# BatTest.net
KiCad netlist of a schematic drawn in Altium Designer
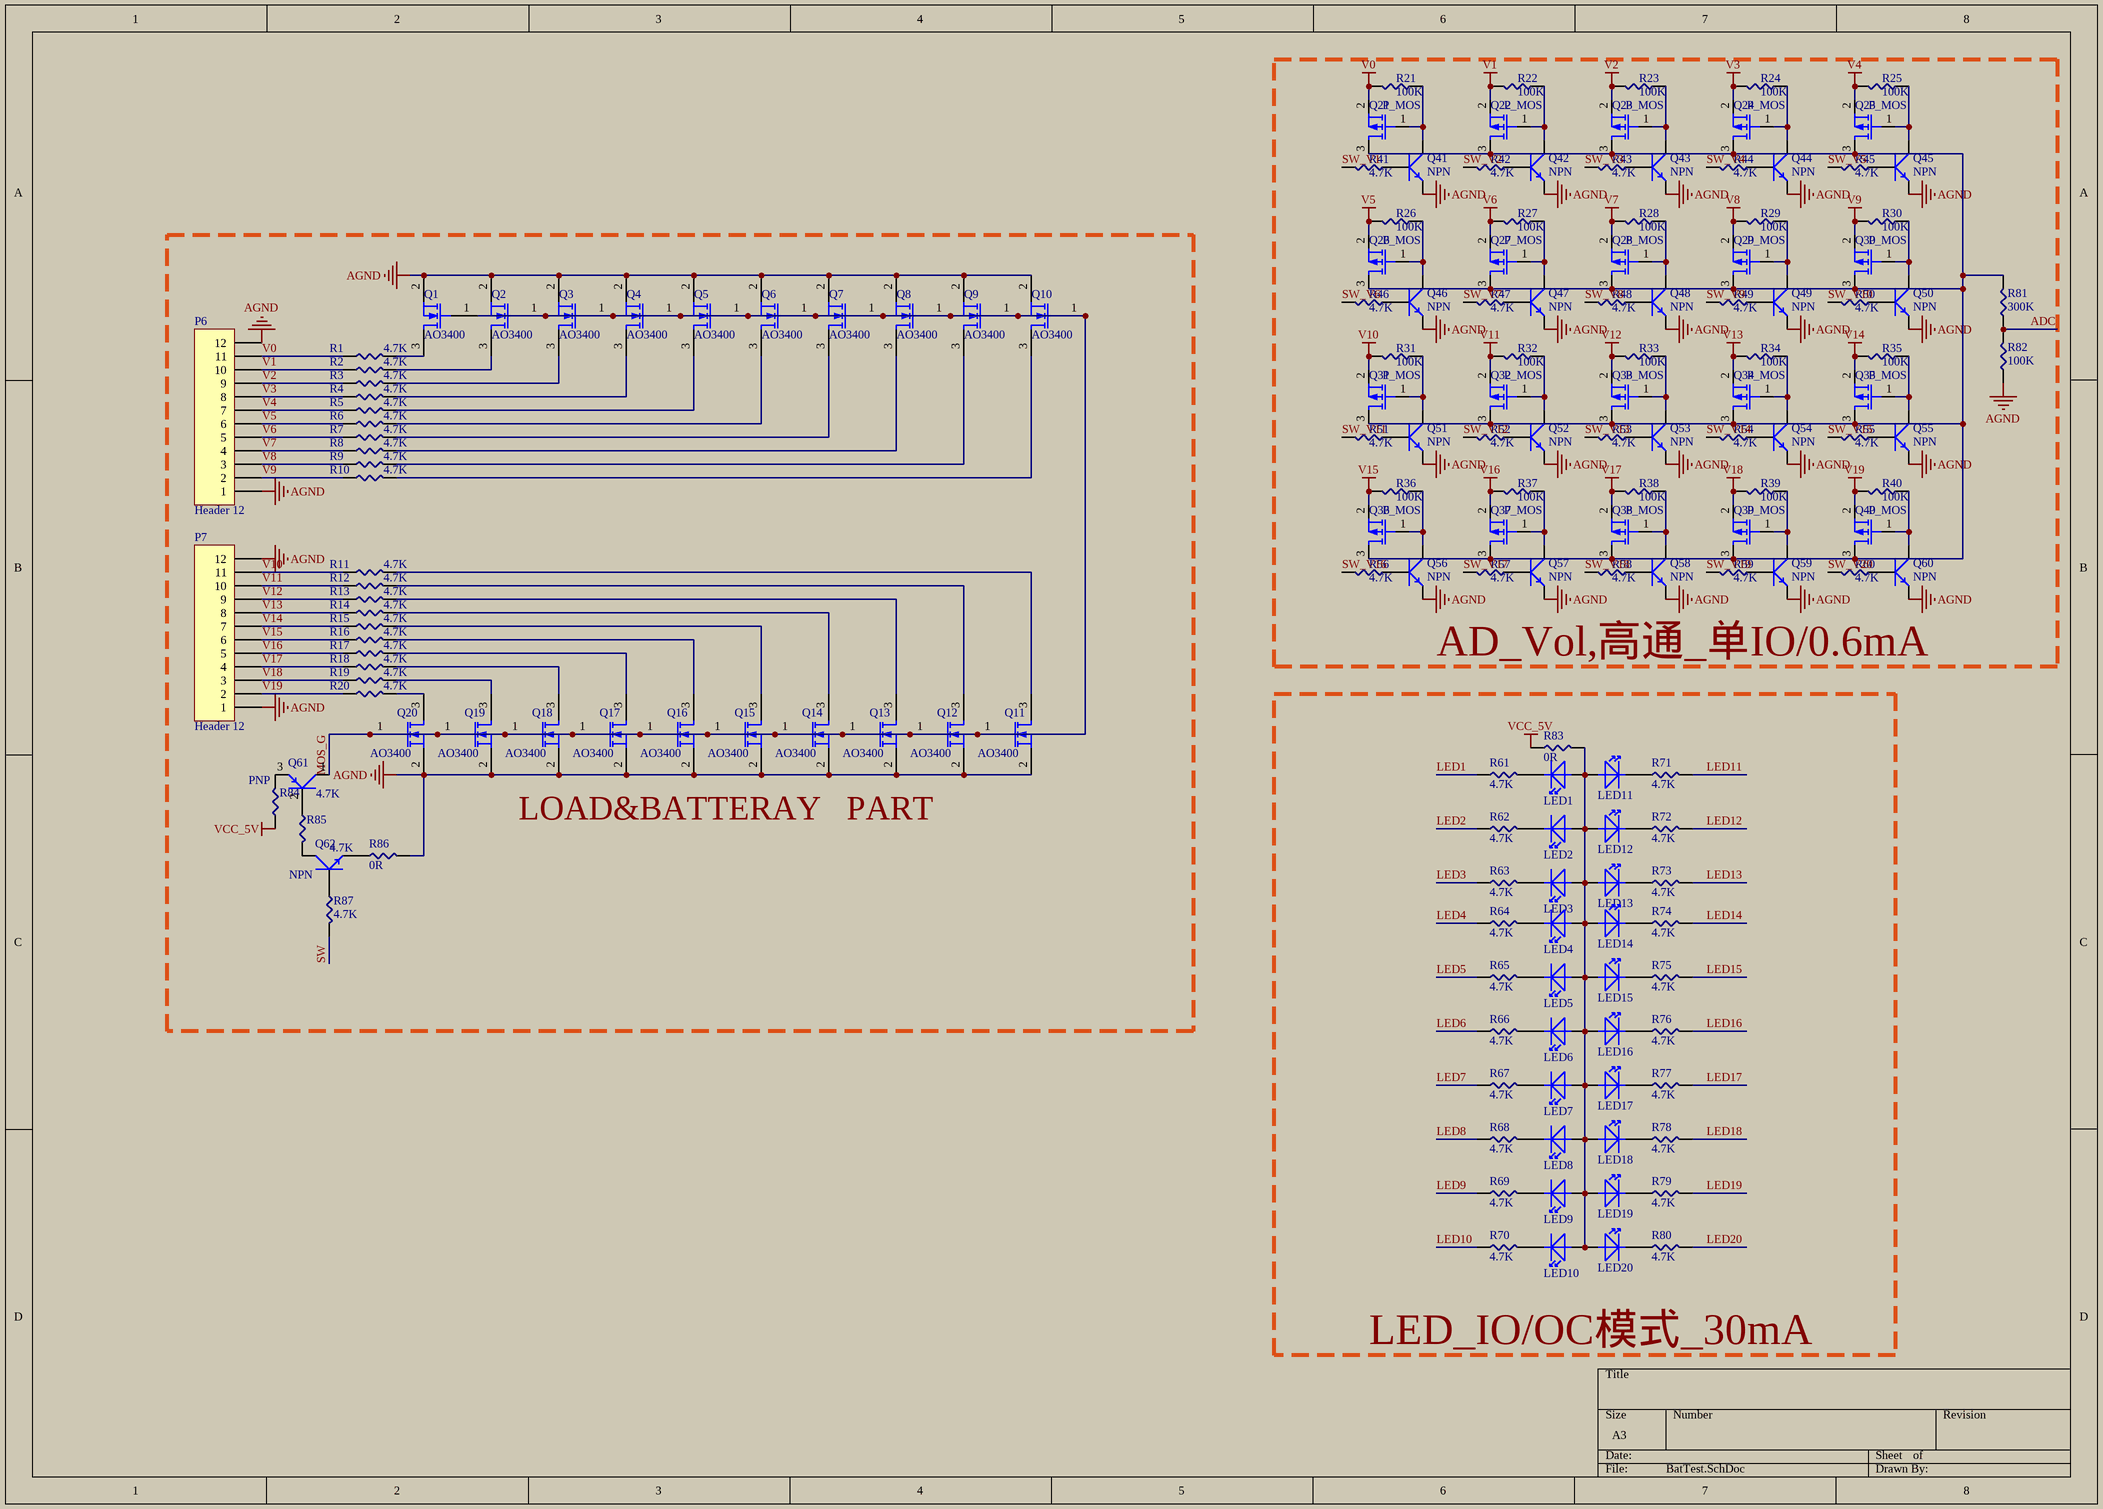
[diagram p0: BatTest.SchDoc]

(export (version "E")
  (design (tool "Eeschema 10.0.6"))
  (components
    (comp (ref "LED1")
      (value "SMD-LED")
      (footprint "DIODE-0603")
      (description "LED")
      (libsource (lib "XXDZ") (part "LED"))
    )
    (comp (ref "LED2")
      (value "SMD-LED")
      (footprint "DIODE-0603")
      (description "LED")
      (libsource (lib "XXDZ") (part "LED"))
    )
    (comp (ref "LED3")
      (value "SMD-LED")
      (footprint "DIODE-0603")
      (description "LED")
      (libsource (lib "XXDZ") (part "LED"))
    )
    (comp (ref "LED4")
      (value "SMD-LED")
      (footprint "DIODE-0603")
      (description "LED")
      (libsource (lib "XXDZ") (part "LED"))
    )
    (comp (ref "LED5")
      (value "SMD-LED")
      (footprint "DIODE-0603")
      (description "LED")
      (libsource (lib "XXDZ") (part "LED"))
    )
    (comp (ref "LED6")
      (value "SMD-LED")
      (footprint "DIODE-0603")
      (description "LED")
      (libsource (lib "XXDZ") (part "LED"))
    )
    (comp (ref "LED7")
      (value "SMD-LED")
      (footprint "DIODE-0603")
      (description "LED")
      (libsource (lib "XXDZ") (part "LED"))
    )
    (comp (ref "LED8")
      (value "SMD-LED")
      (footprint "DIODE-0603")
      (description "LED")
      (libsource (lib "XXDZ") (part "LED"))
    )
    (comp (ref "LED9")
      (value "SMD-LED")
      (footprint "DIODE-0603")
      (description "LED")
      (libsource (lib "XXDZ") (part "LED"))
    )
    (comp (ref "LED10")
      (value "SMD-LED")
      (footprint "DIODE-0603")
      (description "LED")
      (libsource (lib "XXDZ") (part "LED"))
    )
    (comp (ref "LED11")
      (value "SMD-LED")
      (footprint "DIODE-0603")
      (description "LED")
      (libsource (lib "XXDZ") (part "LED"))
    )
    (comp (ref "LED12")
      (value "SMD-LED")
      (footprint "DIODE-0603")
      (description "LED")
      (libsource (lib "XXDZ") (part "LED"))
    )
    (comp (ref "LED13")
      (value "SMD-LED")
      (footprint "DIODE-0603")
      (description "LED")
      (libsource (lib "XXDZ") (part "LED"))
    )
    (comp (ref "LED14")
      (value "SMD-LED")
      (footprint "DIODE-0603")
      (description "LED")
      (libsource (lib "XXDZ") (part "LED"))
    )
    (comp (ref "LED15")
      (value "SMD-LED")
      (footprint "DIODE-0603")
      (description "LED")
      (libsource (lib "XXDZ") (part "LED"))
    )
    (comp (ref "LED16")
      (value "SMD-LED")
      (footprint "DIODE-0603")
      (description "LED")
      (libsource (lib "XXDZ") (part "LED"))
    )
    (comp (ref "LED17")
      (value "SMD-LED")
      (footprint "DIODE-0603")
      (description "LED")
      (libsource (lib "XXDZ") (part "LED"))
    )
    (comp (ref "LED18")
      (value "SMD-LED")
      (footprint "DIODE-0603")
      (description "LED")
      (libsource (lib "XXDZ") (part "LED"))
    )
    (comp (ref "LED19")
      (value "SMD-LED")
      (footprint "DIODE-0603")
      (description "LED")
      (libsource (lib "XXDZ") (part "LED"))
    )
    (comp (ref "LED20")
      (value "SMD-LED")
      (footprint "DIODE-0603")
      (description "LED")
      (libsource (lib "XXDZ") (part "LED"))
    )
    (comp (ref "P6")
      (value "Header 12")
      (footprint "HDR1X12")
      (description "Header, 12-Pin")
      (fields (field (name "PUBLISHER") "Altium Limited"))
      (libsource (lib "Miscellaneous Connectors") (part "Header 12"))
    )
    (comp (ref "P7")
      (value "Header 12")
      (footprint "HDR1X12")
      (description "Header, 12-Pin")
      (fields (field (name "PUBLISHER") "Altium Limited"))
      (libsource (lib "Miscellaneous Connectors") (part "Header 12"))
    )
    (comp (ref "Q1") (value "AO3400") (footprint "SOT-23-MOS") (libsource (lib "MySchlib1") (part "N_MOS")))
    (comp (ref "Q2") (value "AO3400") (footprint "SOT-23-MOS") (libsource (lib "MySchlib1") (part "N_MOS")))
    (comp (ref "Q3") (value "AO3400") (footprint "SOT-23-MOS") (libsource (lib "MySchlib1") (part "N_MOS")))
    (comp (ref "Q4") (value "AO3400") (footprint "SOT-23-MOS") (libsource (lib "MySchlib1") (part "N_MOS")))
    (comp (ref "Q5") (value "AO3400") (footprint "SOT-23-MOS") (libsource (lib "MySchlib1") (part "N_MOS")))
    (comp (ref "Q6") (value "AO3400") (footprint "SOT-23-MOS") (libsource (lib "MySchlib1") (part "N_MOS")))
    (comp (ref "Q7") (value "AO3400") (footprint "SOT-23-MOS") (libsource (lib "MySchlib1") (part "N_MOS")))
    (comp (ref "Q8") (value "AO3400") (footprint "SOT-23-MOS") (libsource (lib "MySchlib1") (part "N_MOS")))
    (comp (ref "Q9") (value "AO3400") (footprint "SOT-23-MOS") (libsource (lib "MySchlib1") (part "N_MOS")))
    (comp (ref "Q10") (value "AO3400") (footprint "SOT-23-MOS") (libsource (lib "MySchlib1") (part "N_MOS")))
    (comp (ref "Q11") (value "AO3400") (footprint "SOT-23-MOS") (libsource (lib "MySchlib1") (part "N_MOS")))
    (comp (ref "Q12") (value "AO3400") (footprint "SOT-23-MOS") (libsource (lib "MySchlib1") (part "N_MOS")))
    (comp (ref "Q13") (value "AO3400") (footprint "SOT-23-MOS") (libsource (lib "MySchlib1") (part "N_MOS")))
    (comp (ref "Q14") (value "AO3400") (footprint "SOT-23-MOS") (libsource (lib "MySchlib1") (part "N_MOS")))
    (comp (ref "Q15") (value "AO3400") (footprint "SOT-23-MOS") (libsource (lib "MySchlib1") (part "N_MOS")))
    (comp (ref "Q16") (value "AO3400") (footprint "SOT-23-MOS") (libsource (lib "MySchlib1") (part "N_MOS")))
    (comp (ref "Q17") (value "AO3400") (footprint "SOT-23-MOS") (libsource (lib "MySchlib1") (part "N_MOS")))
    (comp (ref "Q18") (value "AO3400") (footprint "SOT-23-MOS") (libsource (lib "MySchlib1") (part "N_MOS")))
    (comp (ref "Q19") (value "AO3400") (footprint "SOT-23-MOS") (libsource (lib "MySchlib1") (part "N_MOS")))
    (comp (ref "Q20") (value "AO3400") (footprint "SOT-23-MOS") (libsource (lib "MySchlib1") (part "N_MOS")))
    (comp (ref "Q21") (value "P_MOS") (footprint "SOT-23-MOS") (libsource (lib "MySchlib2") (part "P_MOS")))
    (comp (ref "Q22") (value "P_MOS") (footprint "SOT-23-MOS") (libsource (lib "MySchlib2") (part "P_MOS")))
    (comp (ref "Q23") (value "P_MOS") (footprint "SOT-23-MOS") (libsource (lib "MySchlib2") (part "P_MOS")))
    (comp (ref "Q24") (value "P_MOS") (footprint "SOT-23-MOS") (libsource (lib "MySchlib2") (part "P_MOS")))
    (comp (ref "Q25") (value "P_MOS") (footprint "SOT-23-MOS") (libsource (lib "MySchlib2") (part "P_MOS")))
    (comp (ref "Q26") (value "P_MOS") (footprint "SOT-23-MOS") (libsource (lib "MySchlib2") (part "P_MOS")))
    (comp (ref "Q27") (value "P_MOS") (footprint "SOT-23-MOS") (libsource (lib "MySchlib2") (part "P_MOS")))
    (comp (ref "Q28") (value "P_MOS") (footprint "SOT-23-MOS") (libsource (lib "MySchlib2") (part "P_MOS")))
    (comp (ref "Q29") (value "P_MOS") (footprint "SOT-23-MOS") (libsource (lib "MySchlib2") (part "P_MOS")))
    (comp (ref "Q30") (value "P_MOS") (footprint "SOT-23-MOS") (libsource (lib "MySchlib2") (part "P_MOS")))
    (comp (ref "Q31") (value "P_MOS") (footprint "SOT-23-MOS") (libsource (lib "MySchlib2") (part "P_MOS")))
    (comp (ref "Q32") (value "P_MOS") (footprint "SOT-23-MOS") (libsource (lib "MySchlib2") (part "P_MOS")))
    (comp (ref "Q33") (value "P_MOS") (footprint "SOT-23-MOS") (libsource (lib "MySchlib2") (part "P_MOS")))
    (comp (ref "Q34") (value "P_MOS") (footprint "SOT-23-MOS") (libsource (lib "MySchlib2") (part "P_MOS")))
    (comp (ref "Q35") (value "P_MOS") (footprint "SOT-23-MOS") (libsource (lib "MySchlib2") (part "P_MOS")))
    (comp (ref "Q36") (value "P_MOS") (footprint "SOT-23-MOS") (libsource (lib "MySchlib2") (part "P_MOS")))
    (comp (ref "Q37") (value "P_MOS") (footprint "SOT-23-MOS") (libsource (lib "MySchlib2") (part "P_MOS")))
    (comp (ref "Q38") (value "P_MOS") (footprint "SOT-23-MOS") (libsource (lib "MySchlib2") (part "P_MOS")))
    (comp (ref "Q39") (value "P_MOS") (footprint "SOT-23-MOS") (libsource (lib "MySchlib2") (part "P_MOS")))
    (comp (ref "Q40") (value "P_MOS") (footprint "SOT-23-MOS") (libsource (lib "MySchlib2") (part "P_MOS")))
    (comp (ref "Q41")
      (value "NPN")
      (footprint "SOT-23")
      (description "S8550-J3Y")
      (fields (field (name "Comment") "SMD-TRAN"))
      (libsource (lib "XXDZ") (part "NPN"))
    )
    (comp (ref "Q42")
      (value "NPN")
      (footprint "SOT-23")
      (description "S8550-J3Y")
      (fields (field (name "Comment") "SMD-TRAN"))
      (libsource (lib "XXDZ") (part "NPN"))
    )
    (comp (ref "Q43")
      (value "NPN")
      (footprint "SOT-23")
      (description "S8550-J3Y")
      (fields (field (name "Comment") "SMD-TRAN"))
      (libsource (lib "XXDZ") (part "NPN"))
    )
    (comp (ref "Q44")
      (value "NPN")
      (footprint "SOT-23")
      (description "S8550-J3Y")
      (fields (field (name "Comment") "SMD-TRAN"))
      (libsource (lib "XXDZ") (part "NPN"))
    )
    (comp (ref "Q45")
      (value "NPN")
      (footprint "SOT-23")
      (description "S8550-J3Y")
      (fields (field (name "Comment") "SMD-TRAN"))
      (libsource (lib "XXDZ") (part "NPN"))
    )
    (comp (ref "Q46")
      (value "NPN")
      (footprint "SOT-23")
      (description "S8550-J3Y")
      (fields (field (name "Comment") "SMD-TRAN"))
      (libsource (lib "XXDZ") (part "NPN"))
    )
    (comp (ref "Q47")
      (value "NPN")
      (footprint "SOT-23")
      (description "S8550-J3Y")
      (fields (field (name "Comment") "SMD-TRAN"))
      (libsource (lib "XXDZ") (part "NPN"))
    )
    (comp (ref "Q48")
      (value "NPN")
      (footprint "SOT-23")
      (description "S8550-J3Y")
      (fields (field (name "Comment") "SMD-TRAN"))
      (libsource (lib "XXDZ") (part "NPN"))
    )
    (comp (ref "Q49")
      (value "NPN")
      (footprint "SOT-23")
      (description "S8550-J3Y")
      (fields (field (name "Comment") "SMD-TRAN"))
      (libsource (lib "XXDZ") (part "NPN"))
    )
    (comp (ref "Q50")
      (value "NPN")
      (footprint "SOT-23")
      (description "S8550-J3Y")
      (fields (field (name "Comment") "SMD-TRAN"))
      (libsource (lib "XXDZ") (part "NPN"))
    )
    (comp (ref "Q51")
      (value "NPN")
      (footprint "SOT-23")
      (description "S8550-J3Y")
      (fields (field (name "Comment") "SMD-TRAN"))
      (libsource (lib "XXDZ") (part "NPN"))
    )
    (comp (ref "Q52")
      (value "NPN")
      (footprint "SOT-23")
      (description "S8550-J3Y")
      (fields (field (name "Comment") "SMD-TRAN"))
      (libsource (lib "XXDZ") (part "NPN"))
    )
    (comp (ref "Q53")
      (value "NPN")
      (footprint "SOT-23")
      (description "S8550-J3Y")
      (fields (field (name "Comment") "SMD-TRAN"))
      (libsource (lib "XXDZ") (part "NPN"))
    )
    (comp (ref "Q54")
      (value "NPN")
      (footprint "SOT-23")
      (description "S8550-J3Y")
      (fields (field (name "Comment") "SMD-TRAN"))
      (libsource (lib "XXDZ") (part "NPN"))
    )
    (comp (ref "Q55")
      (value "NPN")
      (footprint "SOT-23")
      (description "S8550-J3Y")
      (fields (field (name "Comment") "SMD-TRAN"))
      (libsource (lib "XXDZ") (part "NPN"))
    )
    (comp (ref "Q56")
      (value "NPN")
      (footprint "SOT-23")
      (description "S8550-J3Y")
      (fields (field (name "Comment") "SMD-TRAN"))
      (libsource (lib "XXDZ") (part "NPN"))
    )
    (comp (ref "Q57")
      (value "NPN")
      (footprint "SOT-23")
      (description "S8550-J3Y")
      (fields (field (name "Comment") "SMD-TRAN"))
      (libsource (lib "XXDZ") (part "NPN"))
    )
    (comp (ref "Q58")
      (value "NPN")
      (footprint "SOT-23")
      (description "S8550-J3Y")
      (fields (field (name "Comment") "SMD-TRAN"))
      (libsource (lib "XXDZ") (part "NPN"))
    )
    (comp (ref "Q59")
      (value "NPN")
      (footprint "SOT-23")
      (description "S8550-J3Y")
      (fields (field (name "Comment") "SMD-TRAN"))
      (libsource (lib "XXDZ") (part "NPN"))
    )
    (comp (ref "Q60")
      (value "NPN")
      (footprint "SOT-23")
      (description "S8550-J3Y")
      (fields (field (name "Comment") "SMD-TRAN"))
      (libsource (lib "XXDZ") (part "NPN"))
    )
    (comp (ref "Q61") (value "PNP") (footprint "SOT-23") (libsource (lib "XXDZ") (part "PNP")))
    (comp (ref "Q62")
      (value "NPN")
      (footprint "SOT-23")
      (description "S8550-J3Y")
      (fields (field (name "Comment") "SMD-TRAN"))
      (libsource (lib "XXDZ") (part "NPN"))
    )
    (comp (ref "R1")
      (value "4.7K")
      (footprint "C1206")
      (description "Power Resistance")
      (fields (field (name "Comment") "Resistance"))
      (libsource (lib "XXDZ") (part "Resistance"))
    )
    (comp (ref "R2")
      (value "4.7K")
      (footprint "C1206")
      (description "Power Resistance")
      (fields (field (name "Comment") "Resistance"))
      (libsource (lib "XXDZ") (part "Resistance"))
    )
    (comp (ref "R3")
      (value "4.7K")
      (footprint "C1206")
      (description "Power Resistance")
      (fields (field (name "Comment") "Resistance"))
      (libsource (lib "XXDZ") (part "Resistance"))
    )
    (comp (ref "R4")
      (value "4.7K")
      (footprint "C1206")
      (description "Power Resistance")
      (fields (field (name "Comment") "Resistance"))
      (libsource (lib "XXDZ") (part "Resistance"))
    )
    (comp (ref "R5")
      (value "4.7K")
      (footprint "C1206")
      (description "Power Resistance")
      (fields (field (name "Comment") "Resistance"))
      (libsource (lib "XXDZ") (part "Resistance"))
    )
    (comp (ref "R6")
      (value "4.7K")
      (footprint "C1206")
      (description "Power Resistance")
      (fields (field (name "Comment") "Resistance"))
      (libsource (lib "XXDZ") (part "Resistance"))
    )
    (comp (ref "R7")
      (value "4.7K")
      (footprint "C1206")
      (description "Power Resistance")
      (fields (field (name "Comment") "Resistance"))
      (libsource (lib "XXDZ") (part "Resistance"))
    )
    (comp (ref "R8")
      (value "4.7K")
      (footprint "C1206")
      (description "Power Resistance")
      (fields (field (name "Comment") "Resistance"))
      (libsource (lib "XXDZ") (part "Resistance"))
    )
    (comp (ref "R9")
      (value "4.7K")
      (footprint "C1206")
      (description "Power Resistance")
      (fields (field (name "Comment") "Resistance"))
      (libsource (lib "XXDZ") (part "Resistance"))
    )
    (comp (ref "R10")
      (value "4.7K")
      (footprint "C1206")
      (description "Power Resistance")
      (fields (field (name "Comment") "Resistance"))
      (libsource (lib "XXDZ") (part "Resistance"))
    )
    (comp (ref "R11")
      (value "4.7K")
      (footprint "C1206")
      (description "Power Resistance")
      (fields (field (name "Comment") "Resistance"))
      (libsource (lib "XXDZ") (part "Resistance"))
    )
    (comp (ref "R12")
      (value "4.7K")
      (footprint "C1206")
      (description "Power Resistance")
      (fields (field (name "Comment") "Resistance"))
      (libsource (lib "XXDZ") (part "Resistance"))
    )
    (comp (ref "R13")
      (value "4.7K")
      (footprint "C1206")
      (description "Power Resistance")
      (fields (field (name "Comment") "Resistance"))
      (libsource (lib "XXDZ") (part "Resistance"))
    )
    (comp (ref "R14")
      (value "4.7K")
      (footprint "C1206")
      (description "Power Resistance")
      (fields (field (name "Comment") "Resistance"))
      (libsource (lib "XXDZ") (part "Resistance"))
    )
    (comp (ref "R15")
      (value "4.7K")
      (footprint "C1206")
      (description "Power Resistance")
      (fields (field (name "Comment") "Resistance"))
      (libsource (lib "XXDZ") (part "Resistance"))
    )
    (comp (ref "R16")
      (value "4.7K")
      (footprint "C1206")
      (description "Power Resistance")
      (fields (field (name "Comment") "Resistance"))
      (libsource (lib "XXDZ") (part "Resistance"))
    )
    (comp (ref "R17")
      (value "4.7K")
      (footprint "C1206")
      (description "Power Resistance")
      (fields (field (name "Comment") "Resistance"))
      (libsource (lib "XXDZ") (part "Resistance"))
    )
    (comp (ref "R18")
      (value "4.7K")
      (footprint "C1206")
      (description "Power Resistance")
      (fields (field (name "Comment") "Resistance"))
      (libsource (lib "XXDZ") (part "Resistance"))
    )
    (comp (ref "R19")
      (value "4.7K")
      (footprint "C1206")
      (description "Power Resistance")
      (fields (field (name "Comment") "Resistance"))
      (libsource (lib "XXDZ") (part "Resistance"))
    )
    (comp (ref "R20")
      (value "4.7K")
      (footprint "C1206")
      (description "Power Resistance")
      (fields (field (name "Comment") "Resistance"))
      (libsource (lib "XXDZ") (part "Resistance"))
    )
    (comp (ref "R21")
      (value "100K")
      (footprint "R_0603")
      (description "Power Resistance")
      (fields (field (name "Comment") "Resistance"))
      (libsource (lib "XXDZ") (part "Resistance"))
    )
    (comp (ref "R22")
      (value "100K")
      (footprint "R_0603")
      (description "Power Resistance")
      (fields (field (name "Comment") "Resistance"))
      (libsource (lib "XXDZ") (part "Resistance"))
    )
    (comp (ref "R23")
      (value "100K")
      (footprint "R_0603")
      (description "Power Resistance")
      (fields (field (name "Comment") "Resistance"))
      (libsource (lib "XXDZ") (part "Resistance"))
    )
    (comp (ref "R24")
      (value "100K")
      (footprint "R_0603")
      (description "Power Resistance")
      (fields (field (name "Comment") "Resistance"))
      (libsource (lib "XXDZ") (part "Resistance"))
    )
    (comp (ref "R25")
      (value "100K")
      (footprint "R_0603")
      (description "Power Resistance")
      (fields (field (name "Comment") "Resistance"))
      (libsource (lib "XXDZ") (part "Resistance"))
    )
    (comp (ref "R26")
      (value "100K")
      (footprint "R_0603")
      (description "Power Resistance")
      (fields (field (name "Comment") "Resistance"))
      (libsource (lib "XXDZ") (part "Resistance"))
    )
    (comp (ref "R27")
      (value "100K")
      (footprint "R_0603")
      (description "Power Resistance")
      (fields (field (name "Comment") "Resistance"))
      (libsource (lib "XXDZ") (part "Resistance"))
    )
    (comp (ref "R28")
      (value "100K")
      (footprint "R_0603")
      (description "Power Resistance")
      (fields (field (name "Comment") "Resistance"))
      (libsource (lib "XXDZ") (part "Resistance"))
    )
    (comp (ref "R29")
      (value "100K")
      (footprint "R_0603")
      (description "Power Resistance")
      (fields (field (name "Comment") "Resistance"))
      (libsource (lib "XXDZ") (part "Resistance"))
    )
    (comp (ref "R30")
      (value "100K")
      (footprint "R_0603")
      (description "Power Resistance")
      (fields (field (name "Comment") "Resistance"))
      (libsource (lib "XXDZ") (part "Resistance"))
    )
    (comp (ref "R31")
      (value "100K")
      (footprint "R_0603")
      (description "Power Resistance")
      (fields (field (name "Comment") "Resistance"))
      (libsource (lib "XXDZ") (part "Resistance"))
    )
    (comp (ref "R32")
      (value "100K")
      (footprint "R_0603")
      (description "Power Resistance")
      (fields (field (name "Comment") "Resistance"))
      (libsource (lib "XXDZ") (part "Resistance"))
    )
    (comp (ref "R33")
      (value "100K")
      (footprint "R_0603")
      (description "Power Resistance")
      (fields (field (name "Comment") "Resistance"))
      (libsource (lib "XXDZ") (part "Resistance"))
    )
    (comp (ref "R34")
      (value "100K")
      (footprint "R_0603")
      (description "Power Resistance")
      (fields (field (name "Comment") "Resistance"))
      (libsource (lib "XXDZ") (part "Resistance"))
    )
    (comp (ref "R35")
      (value "100K")
      (footprint "R_0603")
      (description "Power Resistance")
      (fields (field (name "Comment") "Resistance"))
      (libsource (lib "XXDZ") (part "Resistance"))
    )
    (comp (ref "R36")
      (value "100K")
      (footprint "R_0603")
      (description "Power Resistance")
      (fields (field (name "Comment") "Resistance"))
      (libsource (lib "XXDZ") (part "Resistance"))
    )
    (comp (ref "R37")
      (value "100K")
      (footprint "R_0603")
      (description "Power Resistance")
      (fields (field (name "Comment") "Resistance"))
      (libsource (lib "XXDZ") (part "Resistance"))
    )
    (comp (ref "R38")
      (value "100K")
      (footprint "R_0603")
      (description "Power Resistance")
      (fields (field (name "Comment") "Resistance"))
      (libsource (lib "XXDZ") (part "Resistance"))
    )
    (comp (ref "R39")
      (value "100K")
      (footprint "R_0603")
      (description "Power Resistance")
      (fields (field (name "Comment") "Resistance"))
      (libsource (lib "XXDZ") (part "Resistance"))
    )
    (comp (ref "R40")
      (value "100K")
      (footprint "R_0603")
      (description "Power Resistance")
      (fields (field (name "Comment") "Resistance"))
      (libsource (lib "XXDZ") (part "Resistance"))
    )
    (comp (ref "R41")
      (value "4.7K")
      (footprint "R_0603")
      (description "Power Resistance")
      (fields (field (name "Comment") "Resistance"))
      (libsource (lib "XXDZ") (part "Resistance"))
    )
    (comp (ref "R42")
      (value "4.7K")
      (footprint "R_0603")
      (description "Power Resistance")
      (fields (field (name "Comment") "Resistance"))
      (libsource (lib "XXDZ") (part "Resistance"))
    )
    (comp (ref "R43")
      (value "4.7K")
      (footprint "R_0603")
      (description "Power Resistance")
      (fields (field (name "Comment") "Resistance"))
      (libsource (lib "XXDZ") (part "Resistance"))
    )
    (comp (ref "R44")
      (value "4.7K")
      (footprint "R_0603")
      (description "Power Resistance")
      (fields (field (name "Comment") "Resistance"))
      (libsource (lib "XXDZ") (part "Resistance"))
    )
    (comp (ref "R45")
      (value "4.7K")
      (footprint "R_0603")
      (description "Power Resistance")
      (fields (field (name "Comment") "Resistance"))
      (libsource (lib "XXDZ") (part "Resistance"))
    )
    (comp (ref "R46")
      (value "4.7K")
      (footprint "R_0603")
      (description "Power Resistance")
      (fields (field (name "Comment") "Resistance"))
      (libsource (lib "XXDZ") (part "Resistance"))
    )
    (comp (ref "R47")
      (value "4.7K")
      (footprint "R_0603")
      (description "Power Resistance")
      (fields (field (name "Comment") "Resistance"))
      (libsource (lib "XXDZ") (part "Resistance"))
    )
    (comp (ref "R48")
      (value "4.7K")
      (footprint "R_0603")
      (description "Power Resistance")
      (fields (field (name "Comment") "Resistance"))
      (libsource (lib "XXDZ") (part "Resistance"))
    )
    (comp (ref "R49")
      (value "4.7K")
      (footprint "R_0603")
      (description "Power Resistance")
      (fields (field (name "Comment") "Resistance"))
      (libsource (lib "XXDZ") (part "Resistance"))
    )
    (comp (ref "R50")
      (value "4.7K")
      (footprint "R_0603")
      (description "Power Resistance")
      (fields (field (name "Comment") "Resistance"))
      (libsource (lib "XXDZ") (part "Resistance"))
    )
    (comp (ref "R51")
      (value "4.7K")
      (footprint "R_0603")
      (description "Power Resistance")
      (fields (field (name "Comment") "Resistance"))
      (libsource (lib "XXDZ") (part "Resistance"))
    )
    (comp (ref "R52")
      (value "4.7K")
      (footprint "R_0603")
      (description "Power Resistance")
      (fields (field (name "Comment") "Resistance"))
      (libsource (lib "XXDZ") (part "Resistance"))
    )
    (comp (ref "R53")
      (value "4.7K")
      (footprint "R_0603")
      (description "Power Resistance")
      (fields (field (name "Comment") "Resistance"))
      (libsource (lib "XXDZ") (part "Resistance"))
    )
    (comp (ref "R54")
      (value "4.7K")
      (footprint "R_0603")
      (description "Power Resistance")
      (fields (field (name "Comment") "Resistance"))
      (libsource (lib "XXDZ") (part "Resistance"))
    )
    (comp (ref "R55")
      (value "4.7K")
      (footprint "R_0603")
      (description "Power Resistance")
      (fields (field (name "Comment") "Resistance"))
      (libsource (lib "XXDZ") (part "Resistance"))
    )
    (comp (ref "R56")
      (value "4.7K")
      (footprint "R_0603")
      (description "Power Resistance")
      (fields (field (name "Comment") "Resistance"))
      (libsource (lib "XXDZ") (part "Resistance"))
    )
    (comp (ref "R57")
      (value "4.7K")
      (footprint "R_0603")
      (description "Power Resistance")
      (fields (field (name "Comment") "Resistance"))
      (libsource (lib "XXDZ") (part "Resistance"))
    )
    (comp (ref "R58")
      (value "4.7K")
      (footprint "R_0603")
      (description "Power Resistance")
      (fields (field (name "Comment") "Resistance"))
      (libsource (lib "XXDZ") (part "Resistance"))
    )
    (comp (ref "R59")
      (value "4.7K")
      (footprint "R_0603")
      (description "Power Resistance")
      (fields (field (name "Comment") "Resistance"))
      (libsource (lib "XXDZ") (part "Resistance"))
    )
    (comp (ref "R60")
      (value "4.7K")
      (footprint "R_0603")
      (description "Power Resistance")
      (fields (field (name "Comment") "Resistance"))
      (libsource (lib "XXDZ") (part "Resistance"))
    )
    (comp (ref "R61")
      (value "4.7K")
      (footprint "R_0603")
      (description "Power Resistance")
      (fields (field (name "Comment") "Resistance"))
      (libsource (lib "XXDZ") (part "Resistance"))
    )
    (comp (ref "R62")
      (value "4.7K")
      (footprint "R_0603")
      (description "Power Resistance")
      (fields (field (name "Comment") "Resistance"))
      (libsource (lib "XXDZ") (part "Resistance"))
    )
    (comp (ref "R63")
      (value "4.7K")
      (footprint "R_0603")
      (description "Power Resistance")
      (fields (field (name "Comment") "Resistance"))
      (libsource (lib "XXDZ") (part "Resistance"))
    )
    (comp (ref "R64")
      (value "4.7K")
      (footprint "R_0603")
      (description "Power Resistance")
      (fields (field (name "Comment") "Resistance"))
      (libsource (lib "XXDZ") (part "Resistance"))
    )
    (comp (ref "R65")
      (value "4.7K")
      (footprint "R_0603")
      (description "Power Resistance")
      (fields (field (name "Comment") "Resistance"))
      (libsource (lib "XXDZ") (part "Resistance"))
    )
    (comp (ref "R66")
      (value "4.7K")
      (footprint "R_0603")
      (description "Power Resistance")
      (fields (field (name "Comment") "Resistance"))
      (libsource (lib "XXDZ") (part "Resistance"))
    )
    (comp (ref "R67")
      (value "4.7K")
      (footprint "R_0603")
      (description "Power Resistance")
      (fields (field (name "Comment") "Resistance"))
      (libsource (lib "XXDZ") (part "Resistance"))
    )
    (comp (ref "R68")
      (value "4.7K")
      (footprint "R_0603")
      (description "Power Resistance")
      (fields (field (name "Comment") "Resistance"))
      (libsource (lib "XXDZ") (part "Resistance"))
    )
    (comp (ref "R69")
      (value "4.7K")
      (footprint "R_0603")
      (description "Power Resistance")
      (fields (field (name "Comment") "Resistance"))
      (libsource (lib "XXDZ") (part "Resistance"))
    )
    (comp (ref "R70")
      (value "4.7K")
      (footprint "R_0603")
      (description "Power Resistance")
      (fields (field (name "Comment") "Resistance"))
      (libsource (lib "XXDZ") (part "Resistance"))
    )
    (comp (ref "R71")
      (value "4.7K")
      (footprint "R_0603")
      (description "Power Resistance")
      (fields (field (name "Comment") "Resistance"))
      (libsource (lib "XXDZ") (part "Resistance"))
    )
    (comp (ref "R72")
      (value "4.7K")
      (footprint "R_0603")
      (description "Power Resistance")
      (fields (field (name "Comment") "Resistance"))
      (libsource (lib "XXDZ") (part "Resistance"))
    )
    (comp (ref "R73")
      (value "4.7K")
      (footprint "R_0603")
      (description "Power Resistance")
      (fields (field (name "Comment") "Resistance"))
      (libsource (lib "XXDZ") (part "Resistance"))
    )
    (comp (ref "R74")
      (value "4.7K")
      (footprint "R_0603")
      (description "Power Resistance")
      (fields (field (name "Comment") "Resistance"))
      (libsource (lib "XXDZ") (part "Resistance"))
    )
    (comp (ref "R75")
      (value "4.7K")
      (footprint "R_0603")
      (description "Power Resistance")
      (fields (field (name "Comment") "Resistance"))
      (libsource (lib "XXDZ") (part "Resistance"))
    )
    (comp (ref "R76")
      (value "4.7K")
      (footprint "R_0603")
      (description "Power Resistance")
      (fields (field (name "Comment") "Resistance"))
      (libsource (lib "XXDZ") (part "Resistance"))
    )
    (comp (ref "R77")
      (value "4.7K")
      (footprint "R_0603")
      (description "Power Resistance")
      (fields (field (name "Comment") "Resistance"))
      (libsource (lib "XXDZ") (part "Resistance"))
    )
    (comp (ref "R78")
      (value "4.7K")
      (footprint "R_0603")
      (description "Power Resistance")
      (fields (field (name "Comment") "Resistance"))
      (libsource (lib "XXDZ") (part "Resistance"))
    )
    (comp (ref "R79")
      (value "4.7K")
      (footprint "R_0603")
      (description "Power Resistance")
      (fields (field (name "Comment") "Resistance"))
      (libsource (lib "XXDZ") (part "Resistance"))
    )
    (comp (ref "R80")
      (value "4.7K")
      (footprint "R_0603")
      (description "Power Resistance")
      (fields (field (name "Comment") "Resistance"))
      (libsource (lib "XXDZ") (part "Resistance"))
    )
    (comp (ref "R81")
      (value "300K")
      (footprint "R_0603")
      (description "Power Resistance")
      (fields (field (name "Comment") "Resistance"))
      (libsource (lib "XXDZ") (part "Resistance"))
    )
    (comp (ref "R82")
      (value "100K")
      (footprint "R_0603")
      (description "Power Resistance")
      (fields (field (name "Comment") "Resistance"))
      (libsource (lib "XXDZ") (part "Resistance"))
    )
    (comp (ref "R83")
      (value "0R")
      (footprint "R_0603")
      (description "Power Resistance")
      (fields (field (name "Comment") "Resistance"))
      (libsource (lib "XXDZ") (part "Resistance"))
    )
    (comp (ref "R84")
      (value "4.7K")
      (footprint "R_0603")
      (description "Power Resistance")
      (fields (field (name "Comment") "Resistance"))
      (libsource (lib "XXDZ") (part "Resistance"))
    )
    (comp (ref "R85")
      (value "4.7K")
      (footprint "R_0603")
      (description "Power Resistance")
      (fields (field (name "Comment") "Resistance"))
      (libsource (lib "XXDZ") (part "Resistance"))
    )
    (comp (ref "R86")
      (value "0R")
      (footprint "R_0603")
      (description "Power Resistance")
      (fields (field (name "Comment") "Resistance"))
      (libsource (lib "XXDZ") (part "Resistance"))
    )
    (comp (ref "R87")
      (value "4.7K")
      (footprint "R_0603")
      (description "Power Resistance")
      (fields (field (name "Comment") "Resistance"))
      (libsource (lib "XXDZ") (part "Resistance"))
    )
  )
  (nets
    (net (code "1") (name "/ADC") (class "Default")
      (node (ref "R81") (pin "1") (pinfunction "1_1") (pintype "passive"))
      (node (ref "R82") (pin "2") (pinfunction "2_2") (pintype "passive"))
    )
    (net (code "2") (name "/LED1") (class "Default")
      (node (ref "R61") (pin "1") (pinfunction "1_1") (pintype "passive"))
    )
    (net (code "3") (name "/LED2") (class "Default")
      (node (ref "R62") (pin "1") (pinfunction "1_1") (pintype "passive"))
    )
    (net (code "4") (name "/LED3") (class "Default")
      (node (ref "R63") (pin "1") (pinfunction "1_1") (pintype "passive"))
    )
    (net (code "5") (name "/LED4") (class "Default")
      (node (ref "R64") (pin "1") (pinfunction "1_1") (pintype "passive"))
    )
    (net (code "6") (name "/LED5") (class "Default")
      (node (ref "R65") (pin "1") (pinfunction "1_1") (pintype "passive"))
    )
    (net (code "7") (name "/LED6") (class "Default")
      (node (ref "R66") (pin "1") (pinfunction "1_1") (pintype "passive"))
    )
    (net (code "8") (name "/LED7") (class "Default")
      (node (ref "R67") (pin "1") (pinfunction "1_1") (pintype "passive"))
    )
    (net (code "9") (name "/LED8") (class "Default")
      (node (ref "R68") (pin "1") (pinfunction "1_1") (pintype "passive"))
    )
    (net (code "10") (name "/LED9") (class "Default")
      (node (ref "R69") (pin "1") (pinfunction "1_1") (pintype "passive"))
    )
    (net (code "11") (name "/LED10") (class "Default")
      (node (ref "R70") (pin "1") (pinfunction "1_1") (pintype "passive"))
    )
    (net (code "12") (name "/LED11") (class "Default")
      (node (ref "R71") (pin "2") (pinfunction "2_2") (pintype "passive"))
    )
    (net (code "13") (name "/LED12") (class "Default")
      (node (ref "R72") (pin "2") (pinfunction "2_2") (pintype "passive"))
    )
    (net (code "14") (name "/LED13") (class "Default")
      (node (ref "R73") (pin "2") (pinfunction "2_2") (pintype "passive"))
    )
    (net (code "15") (name "/LED14") (class "Default")
      (node (ref "R74") (pin "2") (pinfunction "2_2") (pintype "passive"))
    )
    (net (code "16") (name "/LED15") (class "Default")
      (node (ref "R75") (pin "2") (pinfunction "2_2") (pintype "passive"))
    )
    (net (code "17") (name "/LED16") (class "Default")
      (node (ref "R76") (pin "2") (pinfunction "2_2") (pintype "passive"))
    )
    (net (code "18") (name "/LED17") (class "Default")
      (node (ref "R77") (pin "2") (pinfunction "2_2") (pintype "passive"))
    )
    (net (code "19") (name "/LED18") (class "Default")
      (node (ref "R78") (pin "2") (pinfunction "2_2") (pintype "passive"))
    )
    (net (code "20") (name "/LED19") (class "Default")
      (node (ref "R79") (pin "2") (pinfunction "2_2") (pintype "passive"))
    )
    (net (code "21") (name "/LED20") (class "Default")
      (node (ref "R80") (pin "2") (pinfunction "2_2") (pintype "passive"))
    )
    (net (code "23") (name "/SW") (class "Default")
      (node (ref "R87") (pin "2") (pinfunction "2_2") (pintype "passive"))
    )
    (net (code "24") (name "/SW_V1") (class "Default")
      (node (ref "R41") (pin "2") (pinfunction "2_2") (pintype "passive"))
    )
    (net (code "25") (name "/SW_V2") (class "Default")
      (node (ref "R42") (pin "2") (pinfunction "2_2") (pintype "passive"))
    )
    (net (code "26") (name "/SW_V3") (class "Default")
      (node (ref "R43") (pin "2") (pinfunction "2_2") (pintype "passive"))
    )
    (net (code "27") (name "/SW_V4") (class "Default")
      (node (ref "R44") (pin "2") (pinfunction "2_2") (pintype "passive"))
    )
    (net (code "28") (name "/SW_V5") (class "Default")
      (node (ref "R45") (pin "2") (pinfunction "2_2") (pintype "passive"))
    )
    (net (code "29") (name "/SW_V6") (class "Default")
      (node (ref "R46") (pin "2") (pinfunction "2_2") (pintype "passive"))
    )
    (net (code "30") (name "/SW_V7") (class "Default")
      (node (ref "R47") (pin "2") (pinfunction "2_2") (pintype "passive"))
    )
    (net (code "31") (name "/SW_V8") (class "Default")
      (node (ref "R48") (pin "2") (pinfunction "2_2") (pintype "passive"))
    )
    (net (code "32") (name "/SW_V9") (class "Default")
      (node (ref "R49") (pin "2") (pinfunction "2_2") (pintype "passive"))
    )
    (net (code "33") (name "/SW_V10") (class "Default")
      (node (ref "R50") (pin "2") (pinfunction "2_2") (pintype "passive"))
    )
    (net (code "34") (name "/SW_V11") (class "Default")
      (node (ref "R51") (pin "2") (pinfunction "2_2") (pintype "passive"))
    )
    (net (code "35") (name "/SW_V12") (class "Default")
      (node (ref "R52") (pin "2") (pinfunction "2_2") (pintype "passive"))
    )
    (net (code "36") (name "/SW_V13") (class "Default")
      (node (ref "R53") (pin "2") (pinfunction "2_2") (pintype "passive"))
    )
    (net (code "37") (name "/SW_V14") (class "Default")
      (node (ref "R54") (pin "2") (pinfunction "2_2") (pintype "passive"))
    )
    (net (code "38") (name "/SW_V15") (class "Default")
      (node (ref "R55") (pin "2") (pinfunction "2_2") (pintype "passive"))
    )
    (net (code "39") (name "/SW_V16") (class "Default")
      (node (ref "R56") (pin "2") (pinfunction "2_2") (pintype "passive"))
    )
    (net (code "40") (name "/SW_V17") (class "Default")
      (node (ref "R57") (pin "2") (pinfunction "2_2") (pintype "passive"))
    )
    (net (code "41") (name "/SW_V18") (class "Default")
      (node (ref "R58") (pin "2") (pinfunction "2_2") (pintype "passive"))
    )
    (net (code "42") (name "/SW_V19") (class "Default")
      (node (ref "R59") (pin "2") (pinfunction "2_2") (pintype "passive"))
    )
    (net (code "43") (name "/SW_V20") (class "Default")
      (node (ref "R60") (pin "2") (pinfunction "2_2") (pintype "passive"))
    )
    (net (code "44") (name "AGND") (class "Default")
      (node (ref "P6") (pin "1") (pinfunction "1_1") (pintype "passive"))
      (node (ref "P6") (pin "12") (pinfunction "12_12") (pintype "passive"))
      (node (ref "P7") (pin "1") (pinfunction "1_1") (pintype "passive"))
      (node (ref "P7") (pin "12") (pinfunction "12_12") (pintype "passive"))
      (node (ref "Q1") (pin "2") (pinfunction "S_2") (pintype "passive"))
      (node (ref "Q10") (pin "2") (pinfunction "S_2") (pintype "passive"))
      (node (ref "Q11") (pin "2") (pinfunction "S_2") (pintype "passive"))
      (node (ref "Q12") (pin "2") (pinfunction "S_2") (pintype "passive"))
      (node (ref "Q13") (pin "2") (pinfunction "S_2") (pintype "passive"))
      (node (ref "Q14") (pin "2") (pinfunction "S_2") (pintype "passive"))
      (node (ref "Q15") (pin "2") (pinfunction "S_2") (pintype "passive"))
      (node (ref "Q16") (pin "2") (pinfunction "S_2") (pintype "passive"))
      (node (ref "Q17") (pin "2") (pinfunction "S_2") (pintype "passive"))
      (node (ref "Q18") (pin "2") (pinfunction "S_2") (pintype "passive"))
      (node (ref "Q19") (pin "2") (pinfunction "S_2") (pintype "passive"))
      (node (ref "Q2") (pin "2") (pinfunction "S_2") (pintype "passive"))
      (node (ref "Q20") (pin "2") (pinfunction "S_2") (pintype "passive"))
      (node (ref "Q3") (pin "2") (pinfunction "S_2") (pintype "passive"))
      (node (ref "Q4") (pin "2") (pinfunction "S_2") (pintype "passive"))
      (node (ref "Q41") (pin "3") (pinfunction "e_3") (pintype "passive"))
      (node (ref "Q42") (pin "3") (pinfunction "e_3") (pintype "passive"))
      (node (ref "Q43") (pin "3") (pinfunction "e_3") (pintype "passive"))
      (node (ref "Q44") (pin "3") (pinfunction "e_3") (pintype "passive"))
      (node (ref "Q45") (pin "3") (pinfunction "e_3") (pintype "passive"))
      (node (ref "Q46") (pin "3") (pinfunction "e_3") (pintype "passive"))
      (node (ref "Q47") (pin "3") (pinfunction "e_3") (pintype "passive"))
      (node (ref "Q48") (pin "3") (pinfunction "e_3") (pintype "passive"))
      (node (ref "Q49") (pin "3") (pinfunction "e_3") (pintype "passive"))
      (node (ref "Q5") (pin "2") (pinfunction "S_2") (pintype "passive"))
      (node (ref "Q50") (pin "3") (pinfunction "e_3") (pintype "passive"))
      (node (ref "Q51") (pin "3") (pinfunction "e_3") (pintype "passive"))
      (node (ref "Q52") (pin "3") (pinfunction "e_3") (pintype "passive"))
      (node (ref "Q53") (pin "3") (pinfunction "e_3") (pintype "passive"))
      (node (ref "Q54") (pin "3") (pinfunction "e_3") (pintype "passive"))
      (node (ref "Q55") (pin "3") (pinfunction "e_3") (pintype "passive"))
      (node (ref "Q56") (pin "3") (pinfunction "e_3") (pintype "passive"))
      (node (ref "Q57") (pin "3") (pinfunction "e_3") (pintype "passive"))
      (node (ref "Q58") (pin "3") (pinfunction "e_3") (pintype "passive"))
      (node (ref "Q59") (pin "3") (pinfunction "e_3") (pintype "passive"))
      (node (ref "Q6") (pin "2") (pinfunction "S_2") (pintype "passive"))
      (node (ref "Q60") (pin "3") (pinfunction "e_3") (pintype "passive"))
      (node (ref "Q7") (pin "2") (pinfunction "S_2") (pintype "passive"))
      (node (ref "Q8") (pin "2") (pinfunction "S_2") (pintype "passive"))
      (node (ref "Q9") (pin "2") (pinfunction "S_2") (pintype "passive"))
      (node (ref "R82") (pin "1") (pinfunction "1_1") (pintype "passive"))
      (node (ref "R86") (pin "2") (pinfunction "2_2") (pintype "passive"))
    )
    (net (code "45") (name "Net-(LED1-A)") (class "Default")
      (node (ref "LED1") (pin "1") (pinfunction "A_1") (pintype "passive"))
      (node (ref "LED10") (pin "1") (pinfunction "A_1") (pintype "passive"))
      (node (ref "LED11") (pin "1") (pinfunction "A_1") (pintype "passive"))
      (node (ref "LED12") (pin "1") (pinfunction "A_1") (pintype "passive"))
      (node (ref "LED13") (pin "1") (pinfunction "A_1") (pintype "passive"))
      (node (ref "LED14") (pin "1") (pinfunction "A_1") (pintype "passive"))
      (node (ref "LED15") (pin "1") (pinfunction "A_1") (pintype "passive"))
      (node (ref "LED16") (pin "1") (pinfunction "A_1") (pintype "passive"))
      (node (ref "LED17") (pin "1") (pinfunction "A_1") (pintype "passive"))
      (node (ref "LED18") (pin "1") (pinfunction "A_1") (pintype "passive"))
      (node (ref "LED19") (pin "1") (pinfunction "A_1") (pintype "passive"))
      (node (ref "LED2") (pin "1") (pinfunction "A_1") (pintype "passive"))
      (node (ref "LED20") (pin "1") (pinfunction "A_1") (pintype "passive"))
      (node (ref "LED3") (pin "1") (pinfunction "A_1") (pintype "passive"))
      (node (ref "LED4") (pin "1") (pinfunction "A_1") (pintype "passive"))
      (node (ref "LED5") (pin "1") (pinfunction "A_1") (pintype "passive"))
      (node (ref "LED6") (pin "1") (pinfunction "A_1") (pintype "passive"))
      (node (ref "LED7") (pin "1") (pinfunction "A_1") (pintype "passive"))
      (node (ref "LED8") (pin "1") (pinfunction "A_1") (pintype "passive"))
      (node (ref "LED9") (pin "1") (pinfunction "A_1") (pintype "passive"))
      (node (ref "R83") (pin "2") (pinfunction "2_2") (pintype "passive"))
    )
    (net (code "46") (name "Net-(LED1-K)") (class "Default")
      (node (ref "LED1") (pin "2") (pinfunction "K_2") (pintype "passive"))
      (node (ref "R61") (pin "2") (pinfunction "2_2") (pintype "passive"))
    )
    (net (code "47") (name "Net-(LED2-K)") (class "Default")
      (node (ref "LED2") (pin "2") (pinfunction "K_2") (pintype "passive"))
      (node (ref "R62") (pin "2") (pinfunction "2_2") (pintype "passive"))
    )
    (net (code "48") (name "Net-(LED3-K)") (class "Default")
      (node (ref "LED3") (pin "2") (pinfunction "K_2") (pintype "passive"))
      (node (ref "R63") (pin "2") (pinfunction "2_2") (pintype "passive"))
    )
    (net (code "49") (name "Net-(LED4-K)") (class "Default")
      (node (ref "LED4") (pin "2") (pinfunction "K_2") (pintype "passive"))
      (node (ref "R64") (pin "2") (pinfunction "2_2") (pintype "passive"))
    )
    (net (code "50") (name "Net-(LED5-K)") (class "Default")
      (node (ref "LED5") (pin "2") (pinfunction "K_2") (pintype "passive"))
      (node (ref "R65") (pin "2") (pinfunction "2_2") (pintype "passive"))
    )
    (net (code "51") (name "Net-(LED6-K)") (class "Default")
      (node (ref "LED6") (pin "2") (pinfunction "K_2") (pintype "passive"))
      (node (ref "R66") (pin "2") (pinfunction "2_2") (pintype "passive"))
    )
    (net (code "52") (name "Net-(LED7-K)") (class "Default")
      (node (ref "LED7") (pin "2") (pinfunction "K_2") (pintype "passive"))
      (node (ref "R67") (pin "2") (pinfunction "2_2") (pintype "passive"))
    )
    (net (code "53") (name "Net-(LED8-K)") (class "Default")
      (node (ref "LED8") (pin "2") (pinfunction "K_2") (pintype "passive"))
      (node (ref "R68") (pin "2") (pinfunction "2_2") (pintype "passive"))
    )
    (net (code "54") (name "Net-(LED9-K)") (class "Default")
      (node (ref "LED9") (pin "2") (pinfunction "K_2") (pintype "passive"))
      (node (ref "R69") (pin "2") (pinfunction "2_2") (pintype "passive"))
    )
    (net (code "55") (name "Net-(LED10-K)") (class "Default")
      (node (ref "LED10") (pin "2") (pinfunction "K_2") (pintype "passive"))
      (node (ref "R70") (pin "2") (pinfunction "2_2") (pintype "passive"))
    )
    (net (code "56") (name "Net-(LED11-K)") (class "Default")
      (node (ref "LED11") (pin "2") (pinfunction "K_2") (pintype "passive"))
      (node (ref "R71") (pin "1") (pinfunction "1_1") (pintype "passive"))
    )
    (net (code "57") (name "Net-(LED12-K)") (class "Default")
      (node (ref "LED12") (pin "2") (pinfunction "K_2") (pintype "passive"))
      (node (ref "R72") (pin "1") (pinfunction "1_1") (pintype "passive"))
    )
    (net (code "58") (name "Net-(LED13-K)") (class "Default")
      (node (ref "LED13") (pin "2") (pinfunction "K_2") (pintype "passive"))
      (node (ref "R73") (pin "1") (pinfunction "1_1") (pintype "passive"))
    )
    (net (code "59") (name "Net-(LED14-K)") (class "Default")
      (node (ref "LED14") (pin "2") (pinfunction "K_2") (pintype "passive"))
      (node (ref "R74") (pin "1") (pinfunction "1_1") (pintype "passive"))
    )
    (net (code "60") (name "Net-(LED15-K)") (class "Default")
      (node (ref "LED15") (pin "2") (pinfunction "K_2") (pintype "passive"))
      (node (ref "R75") (pin "1") (pinfunction "1_1") (pintype "passive"))
    )
    (net (code "61") (name "Net-(LED16-K)") (class "Default")
      (node (ref "LED16") (pin "2") (pinfunction "K_2") (pintype "passive"))
      (node (ref "R76") (pin "1") (pinfunction "1_1") (pintype "passive"))
    )
    (net (code "62") (name "Net-(LED17-K)") (class "Default")
      (node (ref "LED17") (pin "2") (pinfunction "K_2") (pintype "passive"))
      (node (ref "R77") (pin "1") (pinfunction "1_1") (pintype "passive"))
    )
    (net (code "63") (name "Net-(LED18-K)") (class "Default")
      (node (ref "LED18") (pin "2") (pinfunction "K_2") (pintype "passive"))
      (node (ref "R78") (pin "1") (pinfunction "1_1") (pintype "passive"))
    )
    (net (code "64") (name "Net-(LED19-K)") (class "Default")
      (node (ref "LED19") (pin "2") (pinfunction "K_2") (pintype "passive"))
      (node (ref "R79") (pin "1") (pinfunction "1_1") (pintype "passive"))
    )
    (net (code "65") (name "Net-(LED20-K)") (class "Default")
      (node (ref "LED20") (pin "2") (pinfunction "K_2") (pintype "passive"))
      (node (ref "R80") (pin "1") (pinfunction "1_1") (pintype "passive"))
    )
    (net (code "66") (name "Net-(Q1-D)") (class "Default")
      (node (ref "Q1") (pin "3") (pinfunction "D_3") (pintype "passive"))
      (node (ref "R1") (pin "2") (pinfunction "2_2") (pintype "passive"))
    )
    (net (code "67") (name "Net-(Q1-G)") (class "Default")
      (node (ref "Q1") (pin "1") (pinfunction "G_1") (pintype "passive"))
      (node (ref "Q10") (pin "1") (pinfunction "G_1") (pintype "passive"))
      (node (ref "Q11") (pin "1") (pinfunction "G_1") (pintype "passive"))
      (node (ref "Q12") (pin "1") (pinfunction "G_1") (pintype "passive"))
      (node (ref "Q13") (pin "1") (pinfunction "G_1") (pintype "passive"))
      (node (ref "Q14") (pin "1") (pinfunction "G_1") (pintype "passive"))
      (node (ref "Q15") (pin "1") (pinfunction "G_1") (pintype "passive"))
      (node (ref "Q16") (pin "1") (pinfunction "G_1") (pintype "passive"))
      (node (ref "Q17") (pin "1") (pinfunction "G_1") (pintype "passive"))
      (node (ref "Q18") (pin "1") (pinfunction "G_1") (pintype "passive"))
      (node (ref "Q19") (pin "1") (pinfunction "G_1") (pintype "passive"))
      (node (ref "Q2") (pin "1") (pinfunction "G_1") (pintype "passive"))
      (node (ref "Q20") (pin "1") (pinfunction "G_1") (pintype "passive"))
      (node (ref "Q3") (pin "1") (pinfunction "G_1") (pintype "passive"))
      (node (ref "Q4") (pin "1") (pinfunction "G_1") (pintype "passive"))
      (node (ref "Q5") (pin "1") (pinfunction "G_1") (pintype "passive"))
      (node (ref "Q6") (pin "1") (pinfunction "G_1") (pintype "passive"))
      (node (ref "Q61") (pin "1") (pinfunction "c_1") (pintype "passive"))
      (node (ref "Q7") (pin "1") (pinfunction "G_1") (pintype "passive"))
      (node (ref "Q8") (pin "1") (pinfunction "G_1") (pintype "passive"))
      (node (ref "Q9") (pin "1") (pinfunction "G_1") (pintype "passive"))
    )
    (net (code "68") (name "Net-(Q2-D)") (class "Default")
      (node (ref "Q2") (pin "3") (pinfunction "D_3") (pintype "passive"))
      (node (ref "R2") (pin "2") (pinfunction "2_2") (pintype "passive"))
    )
    (net (code "69") (name "Net-(Q3-D)") (class "Default")
      (node (ref "Q3") (pin "3") (pinfunction "D_3") (pintype "passive"))
      (node (ref "R3") (pin "2") (pinfunction "2_2") (pintype "passive"))
    )
    (net (code "70") (name "Net-(Q4-D)") (class "Default")
      (node (ref "Q4") (pin "3") (pinfunction "D_3") (pintype "passive"))
      (node (ref "R4") (pin "2") (pinfunction "2_2") (pintype "passive"))
    )
    (net (code "71") (name "Net-(Q5-D)") (class "Default")
      (node (ref "Q5") (pin "3") (pinfunction "D_3") (pintype "passive"))
      (node (ref "R5") (pin "2") (pinfunction "2_2") (pintype "passive"))
    )
    (net (code "72") (name "Net-(Q6-D)") (class "Default")
      (node (ref "Q6") (pin "3") (pinfunction "D_3") (pintype "passive"))
      (node (ref "R6") (pin "2") (pinfunction "2_2") (pintype "passive"))
    )
    (net (code "73") (name "Net-(Q7-D)") (class "Default")
      (node (ref "Q7") (pin "3") (pinfunction "D_3") (pintype "passive"))
      (node (ref "R7") (pin "2") (pinfunction "2_2") (pintype "passive"))
    )
    (net (code "74") (name "Net-(Q8-D)") (class "Default")
      (node (ref "Q8") (pin "3") (pinfunction "D_3") (pintype "passive"))
      (node (ref "R8") (pin "2") (pinfunction "2_2") (pintype "passive"))
    )
    (net (code "75") (name "Net-(Q9-D)") (class "Default")
      (node (ref "Q9") (pin "3") (pinfunction "D_3") (pintype "passive"))
      (node (ref "R9") (pin "2") (pinfunction "2_2") (pintype "passive"))
    )
    (net (code "76") (name "Net-(Q10-D)") (class "Default")
      (node (ref "Q10") (pin "3") (pinfunction "D_3") (pintype "passive"))
      (node (ref "R10") (pin "2") (pinfunction "2_2") (pintype "passive"))
    )
    (net (code "77") (name "Net-(Q11-D)") (class "Default")
      (node (ref "Q11") (pin "3") (pinfunction "D_3") (pintype "passive"))
      (node (ref "R11") (pin "2") (pinfunction "2_2") (pintype "passive"))
    )
    (net (code "78") (name "Net-(Q12-D)") (class "Default")
      (node (ref "Q12") (pin "3") (pinfunction "D_3") (pintype "passive"))
      (node (ref "R12") (pin "2") (pinfunction "2_2") (pintype "passive"))
    )
    (net (code "79") (name "Net-(Q13-D)") (class "Default")
      (node (ref "Q13") (pin "3") (pinfunction "D_3") (pintype "passive"))
      (node (ref "R13") (pin "2") (pinfunction "2_2") (pintype "passive"))
    )
    (net (code "80") (name "Net-(Q14-D)") (class "Default")
      (node (ref "Q14") (pin "3") (pinfunction "D_3") (pintype "passive"))
      (node (ref "R14") (pin "2") (pinfunction "2_2") (pintype "passive"))
    )
    (net (code "81") (name "Net-(Q15-D)") (class "Default")
      (node (ref "Q15") (pin "3") (pinfunction "D_3") (pintype "passive"))
      (node (ref "R15") (pin "2") (pinfunction "2_2") (pintype "passive"))
    )
    (net (code "82") (name "Net-(Q16-D)") (class "Default")
      (node (ref "Q16") (pin "3") (pinfunction "D_3") (pintype "passive"))
      (node (ref "R16") (pin "2") (pinfunction "2_2") (pintype "passive"))
    )
    (net (code "83") (name "Net-(Q17-D)") (class "Default")
      (node (ref "Q17") (pin "3") (pinfunction "D_3") (pintype "passive"))
      (node (ref "R17") (pin "2") (pinfunction "2_2") (pintype "passive"))
    )
    (net (code "84") (name "Net-(Q18-D)") (class "Default")
      (node (ref "Q18") (pin "3") (pinfunction "D_3") (pintype "passive"))
      (node (ref "R18") (pin "2") (pinfunction "2_2") (pintype "passive"))
    )
    (net (code "85") (name "Net-(Q19-D)") (class "Default")
      (node (ref "Q19") (pin "3") (pinfunction "D_3") (pintype "passive"))
      (node (ref "R19") (pin "2") (pinfunction "2_2") (pintype "passive"))
    )
    (net (code "86") (name "Net-(Q20-D)") (class "Default")
      (node (ref "Q20") (pin "3") (pinfunction "D_3") (pintype "passive"))
      (node (ref "R20") (pin "2") (pinfunction "2_2") (pintype "passive"))
    )
    (net (code "87") (name "Net-(Q21-D)") (class "Default")
      (node (ref "Q21") (pin "3") (pinfunction "D_3") (pintype "passive"))
      (node (ref "Q22") (pin "3") (pinfunction "D_3") (pintype "passive"))
      (node (ref "Q23") (pin "3") (pinfunction "D_3") (pintype "passive"))
      (node (ref "Q24") (pin "3") (pinfunction "D_3") (pintype "passive"))
      (node (ref "Q25") (pin "3") (pinfunction "D_3") (pintype "passive"))
      (node (ref "Q26") (pin "3") (pinfunction "D_3") (pintype "passive"))
      (node (ref "Q27") (pin "3") (pinfunction "D_3") (pintype "passive"))
      (node (ref "Q28") (pin "3") (pinfunction "D_3") (pintype "passive"))
      (node (ref "Q29") (pin "3") (pinfunction "D_3") (pintype "passive"))
      (node (ref "Q30") (pin "3") (pinfunction "D_3") (pintype "passive"))
      (node (ref "Q31") (pin "3") (pinfunction "D_3") (pintype "passive"))
      (node (ref "Q32") (pin "3") (pinfunction "D_3") (pintype "passive"))
      (node (ref "Q33") (pin "3") (pinfunction "D_3") (pintype "passive"))
      (node (ref "Q34") (pin "3") (pinfunction "D_3") (pintype "passive"))
      (node (ref "Q35") (pin "3") (pinfunction "D_3") (pintype "passive"))
      (node (ref "Q36") (pin "3") (pinfunction "D_3") (pintype "passive"))
      (node (ref "Q37") (pin "3") (pinfunction "D_3") (pintype "passive"))
      (node (ref "Q38") (pin "3") (pinfunction "D_3") (pintype "passive"))
      (node (ref "Q39") (pin "3") (pinfunction "D_3") (pintype "passive"))
      (node (ref "Q40") (pin "3") (pinfunction "D_3") (pintype "passive"))
      (node (ref "R81") (pin "2") (pinfunction "2_2") (pintype "passive"))
    )
    (net (code "88") (name "Net-(Q21-G)") (class "Default")
      (node (ref "Q21") (pin "1") (pinfunction "G_1") (pintype "passive"))
      (node (ref "Q41") (pin "1") (pinfunction "c_1") (pintype "passive"))
      (node (ref "R21") (pin "1") (pinfunction "1_1") (pintype "passive"))
    )
    (net (code "89") (name "Net-(Q22-G)") (class "Default")
      (node (ref "Q22") (pin "1") (pinfunction "G_1") (pintype "passive"))
      (node (ref "Q42") (pin "1") (pinfunction "c_1") (pintype "passive"))
      (node (ref "R22") (pin "1") (pinfunction "1_1") (pintype "passive"))
    )
    (net (code "90") (name "Net-(Q23-G)") (class "Default")
      (node (ref "Q23") (pin "1") (pinfunction "G_1") (pintype "passive"))
      (node (ref "Q43") (pin "1") (pinfunction "c_1") (pintype "passive"))
      (node (ref "R23") (pin "1") (pinfunction "1_1") (pintype "passive"))
    )
    (net (code "91") (name "Net-(Q24-G)") (class "Default")
      (node (ref "Q24") (pin "1") (pinfunction "G_1") (pintype "passive"))
      (node (ref "Q44") (pin "1") (pinfunction "c_1") (pintype "passive"))
      (node (ref "R24") (pin "1") (pinfunction "1_1") (pintype "passive"))
    )
    (net (code "92") (name "Net-(Q25-G)") (class "Default")
      (node (ref "Q25") (pin "1") (pinfunction "G_1") (pintype "passive"))
      (node (ref "Q45") (pin "1") (pinfunction "c_1") (pintype "passive"))
      (node (ref "R25") (pin "1") (pinfunction "1_1") (pintype "passive"))
    )
    (net (code "93") (name "Net-(Q26-G)") (class "Default")
      (node (ref "Q26") (pin "1") (pinfunction "G_1") (pintype "passive"))
      (node (ref "Q46") (pin "1") (pinfunction "c_1") (pintype "passive"))
      (node (ref "R26") (pin "1") (pinfunction "1_1") (pintype "passive"))
    )
    (net (code "94") (name "Net-(Q27-G)") (class "Default")
      (node (ref "Q27") (pin "1") (pinfunction "G_1") (pintype "passive"))
      (node (ref "Q47") (pin "1") (pinfunction "c_1") (pintype "passive"))
      (node (ref "R27") (pin "1") (pinfunction "1_1") (pintype "passive"))
    )
    (net (code "95") (name "Net-(Q28-G)") (class "Default")
      (node (ref "Q28") (pin "1") (pinfunction "G_1") (pintype "passive"))
      (node (ref "Q48") (pin "1") (pinfunction "c_1") (pintype "passive"))
      (node (ref "R28") (pin "1") (pinfunction "1_1") (pintype "passive"))
    )
    (net (code "96") (name "Net-(Q29-G)") (class "Default")
      (node (ref "Q29") (pin "1") (pinfunction "G_1") (pintype "passive"))
      (node (ref "Q49") (pin "1") (pinfunction "c_1") (pintype "passive"))
      (node (ref "R29") (pin "1") (pinfunction "1_1") (pintype "passive"))
    )
    (net (code "97") (name "Net-(Q30-G)") (class "Default")
      (node (ref "Q30") (pin "1") (pinfunction "G_1") (pintype "passive"))
      (node (ref "Q50") (pin "1") (pinfunction "c_1") (pintype "passive"))
      (node (ref "R30") (pin "1") (pinfunction "1_1") (pintype "passive"))
    )
    (net (code "98") (name "Net-(Q31-G)") (class "Default")
      (node (ref "Q31") (pin "1") (pinfunction "G_1") (pintype "passive"))
      (node (ref "Q51") (pin "1") (pinfunction "c_1") (pintype "passive"))
      (node (ref "R31") (pin "1") (pinfunction "1_1") (pintype "passive"))
    )
    (net (code "99") (name "Net-(Q32-G)") (class "Default")
      (node (ref "Q32") (pin "1") (pinfunction "G_1") (pintype "passive"))
      (node (ref "Q52") (pin "1") (pinfunction "c_1") (pintype "passive"))
      (node (ref "R32") (pin "1") (pinfunction "1_1") (pintype "passive"))
    )
    (net (code "100") (name "Net-(Q33-G)") (class "Default")
      (node (ref "Q33") (pin "1") (pinfunction "G_1") (pintype "passive"))
      (node (ref "Q53") (pin "1") (pinfunction "c_1") (pintype "passive"))
      (node (ref "R33") (pin "1") (pinfunction "1_1") (pintype "passive"))
    )
    (net (code "101") (name "Net-(Q34-G)") (class "Default")
      (node (ref "Q34") (pin "1") (pinfunction "G_1") (pintype "passive"))
      (node (ref "Q54") (pin "1") (pinfunction "c_1") (pintype "passive"))
      (node (ref "R34") (pin "1") (pinfunction "1_1") (pintype "passive"))
    )
    (net (code "102") (name "Net-(Q35-G)") (class "Default")
      (node (ref "Q35") (pin "1") (pinfunction "G_1") (pintype "passive"))
      (node (ref "Q55") (pin "1") (pinfunction "c_1") (pintype "passive"))
      (node (ref "R35") (pin "1") (pinfunction "1_1") (pintype "passive"))
    )
    (net (code "103") (name "Net-(Q36-G)") (class "Default")
      (node (ref "Q36") (pin "1") (pinfunction "G_1") (pintype "passive"))
      (node (ref "Q56") (pin "1") (pinfunction "c_1") (pintype "passive"))
      (node (ref "R36") (pin "1") (pinfunction "1_1") (pintype "passive"))
    )
    (net (code "104") (name "Net-(Q37-G)") (class "Default")
      (node (ref "Q37") (pin "1") (pinfunction "G_1") (pintype "passive"))
      (node (ref "Q57") (pin "1") (pinfunction "c_1") (pintype "passive"))
      (node (ref "R37") (pin "1") (pinfunction "1_1") (pintype "passive"))
    )
    (net (code "105") (name "Net-(Q38-G)") (class "Default")
      (node (ref "Q38") (pin "1") (pinfunction "G_1") (pintype "passive"))
      (node (ref "Q58") (pin "1") (pinfunction "c_1") (pintype "passive"))
      (node (ref "R38") (pin "1") (pinfunction "1_1") (pintype "passive"))
    )
    (net (code "106") (name "Net-(Q39-G)") (class "Default")
      (node (ref "Q39") (pin "1") (pinfunction "G_1") (pintype "passive"))
      (node (ref "Q59") (pin "1") (pinfunction "c_1") (pintype "passive"))
      (node (ref "R39") (pin "1") (pinfunction "1_1") (pintype "passive"))
    )
    (net (code "107") (name "Net-(Q40-G)") (class "Default")
      (node (ref "Q40") (pin "1") (pinfunction "G_1") (pintype "passive"))
      (node (ref "Q60") (pin "1") (pinfunction "c_1") (pintype "passive"))
      (node (ref "R40") (pin "1") (pinfunction "1_1") (pintype "passive"))
    )
    (net (code "108") (name "Net-(Q41-b)") (class "Default")
      (node (ref "Q41") (pin "2") (pinfunction "b_2") (pintype "passive"))
      (node (ref "R41") (pin "1") (pinfunction "1_1") (pintype "passive"))
    )
    (net (code "109") (name "Net-(Q42-b)") (class "Default")
      (node (ref "Q42") (pin "2") (pinfunction "b_2") (pintype "passive"))
      (node (ref "R42") (pin "1") (pinfunction "1_1") (pintype "passive"))
    )
    (net (code "110") (name "Net-(Q43-b)") (class "Default")
      (node (ref "Q43") (pin "2") (pinfunction "b_2") (pintype "passive"))
      (node (ref "R43") (pin "1") (pinfunction "1_1") (pintype "passive"))
    )
    (net (code "111") (name "Net-(Q44-b)") (class "Default")
      (node (ref "Q44") (pin "2") (pinfunction "b_2") (pintype "passive"))
      (node (ref "R44") (pin "1") (pinfunction "1_1") (pintype "passive"))
    )
    (net (code "112") (name "Net-(Q45-b)") (class "Default")
      (node (ref "Q45") (pin "2") (pinfunction "b_2") (pintype "passive"))
      (node (ref "R45") (pin "1") (pinfunction "1_1") (pintype "passive"))
    )
    (net (code "113") (name "Net-(Q46-b)") (class "Default")
      (node (ref "Q46") (pin "2") (pinfunction "b_2") (pintype "passive"))
      (node (ref "R46") (pin "1") (pinfunction "1_1") (pintype "passive"))
    )
    (net (code "114") (name "Net-(Q47-b)") (class "Default")
      (node (ref "Q47") (pin "2") (pinfunction "b_2") (pintype "passive"))
      (node (ref "R47") (pin "1") (pinfunction "1_1") (pintype "passive"))
    )
    (net (code "115") (name "Net-(Q48-b)") (class "Default")
      (node (ref "Q48") (pin "2") (pinfunction "b_2") (pintype "passive"))
      (node (ref "R48") (pin "1") (pinfunction "1_1") (pintype "passive"))
    )
    (net (code "116") (name "Net-(Q49-b)") (class "Default")
      (node (ref "Q49") (pin "2") (pinfunction "b_2") (pintype "passive"))
      (node (ref "R49") (pin "1") (pinfunction "1_1") (pintype "passive"))
    )
    (net (code "117") (name "Net-(Q50-b)") (class "Default")
      (node (ref "Q50") (pin "2") (pinfunction "b_2") (pintype "passive"))
      (node (ref "R50") (pin "1") (pinfunction "1_1") (pintype "passive"))
    )
    (net (code "118") (name "Net-(Q51-b)") (class "Default")
      (node (ref "Q51") (pin "2") (pinfunction "b_2") (pintype "passive"))
      (node (ref "R51") (pin "1") (pinfunction "1_1") (pintype "passive"))
    )
    (net (code "119") (name "Net-(Q52-b)") (class "Default")
      (node (ref "Q52") (pin "2") (pinfunction "b_2") (pintype "passive"))
      (node (ref "R52") (pin "1") (pinfunction "1_1") (pintype "passive"))
    )
    (net (code "120") (name "Net-(Q53-b)") (class "Default")
      (node (ref "Q53") (pin "2") (pinfunction "b_2") (pintype "passive"))
      (node (ref "R53") (pin "1") (pinfunction "1_1") (pintype "passive"))
    )
    (net (code "121") (name "Net-(Q54-b)") (class "Default")
      (node (ref "Q54") (pin "2") (pinfunction "b_2") (pintype "passive"))
      (node (ref "R54") (pin "1") (pinfunction "1_1") (pintype "passive"))
    )
    (net (code "122") (name "Net-(Q55-b)") (class "Default")
      (node (ref "Q55") (pin "2") (pinfunction "b_2") (pintype "passive"))
      (node (ref "R55") (pin "1") (pinfunction "1_1") (pintype "passive"))
    )
    (net (code "123") (name "Net-(Q56-b)") (class "Default")
      (node (ref "Q56") (pin "2") (pinfunction "b_2") (pintype "passive"))
      (node (ref "R56") (pin "1") (pinfunction "1_1") (pintype "passive"))
    )
    (net (code "124") (name "Net-(Q57-b)") (class "Default")
      (node (ref "Q57") (pin "2") (pinfunction "b_2") (pintype "passive"))
      (node (ref "R57") (pin "1") (pinfunction "1_1") (pintype "passive"))
    )
    (net (code "125") (name "Net-(Q58-b)") (class "Default")
      (node (ref "Q58") (pin "2") (pinfunction "b_2") (pintype "passive"))
      (node (ref "R58") (pin "1") (pinfunction "1_1") (pintype "passive"))
    )
    (net (code "126") (name "Net-(Q59-b)") (class "Default")
      (node (ref "Q59") (pin "2") (pinfunction "b_2") (pintype "passive"))
      (node (ref "R59") (pin "1") (pinfunction "1_1") (pintype "passive"))
    )
    (net (code "127") (name "Net-(Q60-b)") (class "Default")
      (node (ref "Q60") (pin "2") (pinfunction "b_2") (pintype "passive"))
      (node (ref "R60") (pin "1") (pinfunction "1_1") (pintype "passive"))
    )
    (net (code "128") (name "Net-(Q61-b)") (class "Default")
      (node (ref "Q61") (pin "2") (pinfunction "b_2") (pintype "passive"))
      (node (ref "R85") (pin "1") (pinfunction "1_1") (pintype "passive"))
    )
    (net (code "129") (name "Net-(Q61-e)") (class "Default")
      (node (ref "Q61") (pin "3") (pinfunction "e_3") (pintype "passive"))
      (node (ref "R84") (pin "2") (pinfunction "2_2") (pintype "passive"))
    )
    (net (code "130") (name "Net-(Q62-b)") (class "Default")
      (node (ref "Q62") (pin "2") (pinfunction "b_2") (pintype "passive"))
      (node (ref "R87") (pin "1") (pinfunction "1_1") (pintype "passive"))
    )
    (net (code "131") (name "Net-(Q62-c)") (class "Default")
      (node (ref "Q62") (pin "1") (pinfunction "c_1") (pintype "passive"))
      (node (ref "R85") (pin "2") (pinfunction "2_2") (pintype "passive"))
    )
    (net (code "132") (name "Net-(Q62-e)") (class "Default")
      (node (ref "Q62") (pin "3") (pinfunction "e_3") (pintype "passive"))
      (node (ref "R86") (pin "1") (pinfunction "1_1") (pintype "passive"))
    )
    (net (code "133") (name "V0") (class "Default")
      (node (ref "P6") (pin "11") (pinfunction "11_11") (pintype "passive"))
      (node (ref "Q21") (pin "2") (pinfunction "S_2") (pintype "passive"))
      (node (ref "R1") (pin "1") (pinfunction "1_1") (pintype "passive"))
      (node (ref "R21") (pin "2") (pinfunction "2_2") (pintype "passive"))
    )
    (net (code "134") (name "V1") (class "Default")
      (node (ref "P6") (pin "10") (pinfunction "10_10") (pintype "passive"))
      (node (ref "Q22") (pin "2") (pinfunction "S_2") (pintype "passive"))
      (node (ref "R2") (pin "1") (pinfunction "1_1") (pintype "passive"))
      (node (ref "R22") (pin "2") (pinfunction "2_2") (pintype "passive"))
    )
    (net (code "135") (name "V2") (class "Default")
      (node (ref "P6") (pin "9") (pinfunction "9_9") (pintype "passive"))
      (node (ref "Q23") (pin "2") (pinfunction "S_2") (pintype "passive"))
      (node (ref "R23") (pin "2") (pinfunction "2_2") (pintype "passive"))
      (node (ref "R3") (pin "1") (pinfunction "1_1") (pintype "passive"))
    )
    (net (code "136") (name "V3") (class "Default")
      (node (ref "P6") (pin "8") (pinfunction "8_8") (pintype "passive"))
      (node (ref "Q24") (pin "2") (pinfunction "S_2") (pintype "passive"))
      (node (ref "R24") (pin "2") (pinfunction "2_2") (pintype "passive"))
      (node (ref "R4") (pin "1") (pinfunction "1_1") (pintype "passive"))
    )
    (net (code "137") (name "V4") (class "Default")
      (node (ref "P6") (pin "7") (pinfunction "7_7") (pintype "passive"))
      (node (ref "Q25") (pin "2") (pinfunction "S_2") (pintype "passive"))
      (node (ref "R25") (pin "2") (pinfunction "2_2") (pintype "passive"))
      (node (ref "R5") (pin "1") (pinfunction "1_1") (pintype "passive"))
    )
    (net (code "138") (name "V5") (class "Default")
      (node (ref "P6") (pin "6") (pinfunction "6_6") (pintype "passive"))
      (node (ref "Q26") (pin "2") (pinfunction "S_2") (pintype "passive"))
      (node (ref "R26") (pin "2") (pinfunction "2_2") (pintype "passive"))
      (node (ref "R6") (pin "1") (pinfunction "1_1") (pintype "passive"))
    )
    (net (code "139") (name "V6") (class "Default")
      (node (ref "P6") (pin "5") (pinfunction "5_5") (pintype "passive"))
      (node (ref "Q27") (pin "2") (pinfunction "S_2") (pintype "passive"))
      (node (ref "R27") (pin "2") (pinfunction "2_2") (pintype "passive"))
      (node (ref "R7") (pin "1") (pinfunction "1_1") (pintype "passive"))
    )
    (net (code "140") (name "V7") (class "Default")
      (node (ref "P6") (pin "4") (pinfunction "4_4") (pintype "passive"))
      (node (ref "Q28") (pin "2") (pinfunction "S_2") (pintype "passive"))
      (node (ref "R28") (pin "2") (pinfunction "2_2") (pintype "passive"))
      (node (ref "R8") (pin "1") (pinfunction "1_1") (pintype "passive"))
    )
    (net (code "141") (name "V8") (class "Default")
      (node (ref "P6") (pin "3") (pinfunction "3_3") (pintype "passive"))
      (node (ref "Q29") (pin "2") (pinfunction "S_2") (pintype "passive"))
      (node (ref "R29") (pin "2") (pinfunction "2_2") (pintype "passive"))
      (node (ref "R9") (pin "1") (pinfunction "1_1") (pintype "passive"))
    )
    (net (code "142") (name "V9") (class "Default")
      (node (ref "P6") (pin "2") (pinfunction "2_2") (pintype "passive"))
      (node (ref "Q30") (pin "2") (pinfunction "S_2") (pintype "passive"))
      (node (ref "R10") (pin "1") (pinfunction "1_1") (pintype "passive"))
      (node (ref "R30") (pin "2") (pinfunction "2_2") (pintype "passive"))
    )
    (net (code "143") (name "V10") (class "Default")
      (node (ref "P7") (pin "11") (pinfunction "11_11") (pintype "passive"))
      (node (ref "Q31") (pin "2") (pinfunction "S_2") (pintype "passive"))
      (node (ref "R11") (pin "1") (pinfunction "1_1") (pintype "passive"))
      (node (ref "R31") (pin "2") (pinfunction "2_2") (pintype "passive"))
    )
    (net (code "144") (name "V11") (class "Default")
      (node (ref "P7") (pin "10") (pinfunction "10_10") (pintype "passive"))
      (node (ref "Q32") (pin "2") (pinfunction "S_2") (pintype "passive"))
      (node (ref "R12") (pin "1") (pinfunction "1_1") (pintype "passive"))
      (node (ref "R32") (pin "2") (pinfunction "2_2") (pintype "passive"))
    )
    (net (code "145") (name "V12") (class "Default")
      (node (ref "P7") (pin "9") (pinfunction "9_9") (pintype "passive"))
      (node (ref "Q33") (pin "2") (pinfunction "S_2") (pintype "passive"))
      (node (ref "R13") (pin "1") (pinfunction "1_1") (pintype "passive"))
      (node (ref "R33") (pin "2") (pinfunction "2_2") (pintype "passive"))
    )
    (net (code "146") (name "V13") (class "Default")
      (node (ref "P7") (pin "8") (pinfunction "8_8") (pintype "passive"))
      (node (ref "Q34") (pin "2") (pinfunction "S_2") (pintype "passive"))
      (node (ref "R14") (pin "1") (pinfunction "1_1") (pintype "passive"))
      (node (ref "R34") (pin "2") (pinfunction "2_2") (pintype "passive"))
    )
    (net (code "147") (name "V14") (class "Default")
      (node (ref "P7") (pin "7") (pinfunction "7_7") (pintype "passive"))
      (node (ref "Q35") (pin "2") (pinfunction "S_2") (pintype "passive"))
      (node (ref "R15") (pin "1") (pinfunction "1_1") (pintype "passive"))
      (node (ref "R35") (pin "2") (pinfunction "2_2") (pintype "passive"))
    )
    (net (code "148") (name "V15") (class "Default")
      (node (ref "P7") (pin "6") (pinfunction "6_6") (pintype "passive"))
      (node (ref "Q36") (pin "2") (pinfunction "S_2") (pintype "passive"))
      (node (ref "R16") (pin "1") (pinfunction "1_1") (pintype "passive"))
      (node (ref "R36") (pin "2") (pinfunction "2_2") (pintype "passive"))
    )
    (net (code "149") (name "V16") (class "Default")
      (node (ref "P7") (pin "5") (pinfunction "5_5") (pintype "passive"))
      (node (ref "Q37") (pin "2") (pinfunction "S_2") (pintype "passive"))
      (node (ref "R17") (pin "1") (pinfunction "1_1") (pintype "passive"))
      (node (ref "R37") (pin "2") (pinfunction "2_2") (pintype "passive"))
    )
    (net (code "150") (name "V17") (class "Default")
      (node (ref "P7") (pin "4") (pinfunction "4_4") (pintype "passive"))
      (node (ref "Q38") (pin "2") (pinfunction "S_2") (pintype "passive"))
      (node (ref "R18") (pin "1") (pinfunction "1_1") (pintype "passive"))
      (node (ref "R38") (pin "2") (pinfunction "2_2") (pintype "passive"))
    )
    (net (code "151") (name "V18") (class "Default")
      (node (ref "P7") (pin "3") (pinfunction "3_3") (pintype "passive"))
      (node (ref "Q39") (pin "2") (pinfunction "S_2") (pintype "passive"))
      (node (ref "R19") (pin "1") (pinfunction "1_1") (pintype "passive"))
      (node (ref "R39") (pin "2") (pinfunction "2_2") (pintype "passive"))
    )
    (net (code "152") (name "V19") (class "Default")
      (node (ref "P7") (pin "2") (pinfunction "2_2") (pintype "passive"))
      (node (ref "Q40") (pin "2") (pinfunction "S_2") (pintype "passive"))
      (node (ref "R20") (pin "1") (pinfunction "1_1") (pintype "passive"))
      (node (ref "R40") (pin "2") (pinfunction "2_2") (pintype "passive"))
    )
    (net (code "153") (name "VCC_5V") (class "Default")
      (node (ref "R83") (pin "1") (pinfunction "1_1") (pintype "passive"))
      (node (ref "R84") (pin "1") (pinfunction "1_1") (pintype "passive"))
    )
  )
)
